# EEZ_DIB_MUX14D_r1B3.net
KiCad netlist of a schematic drawn in EAGLE
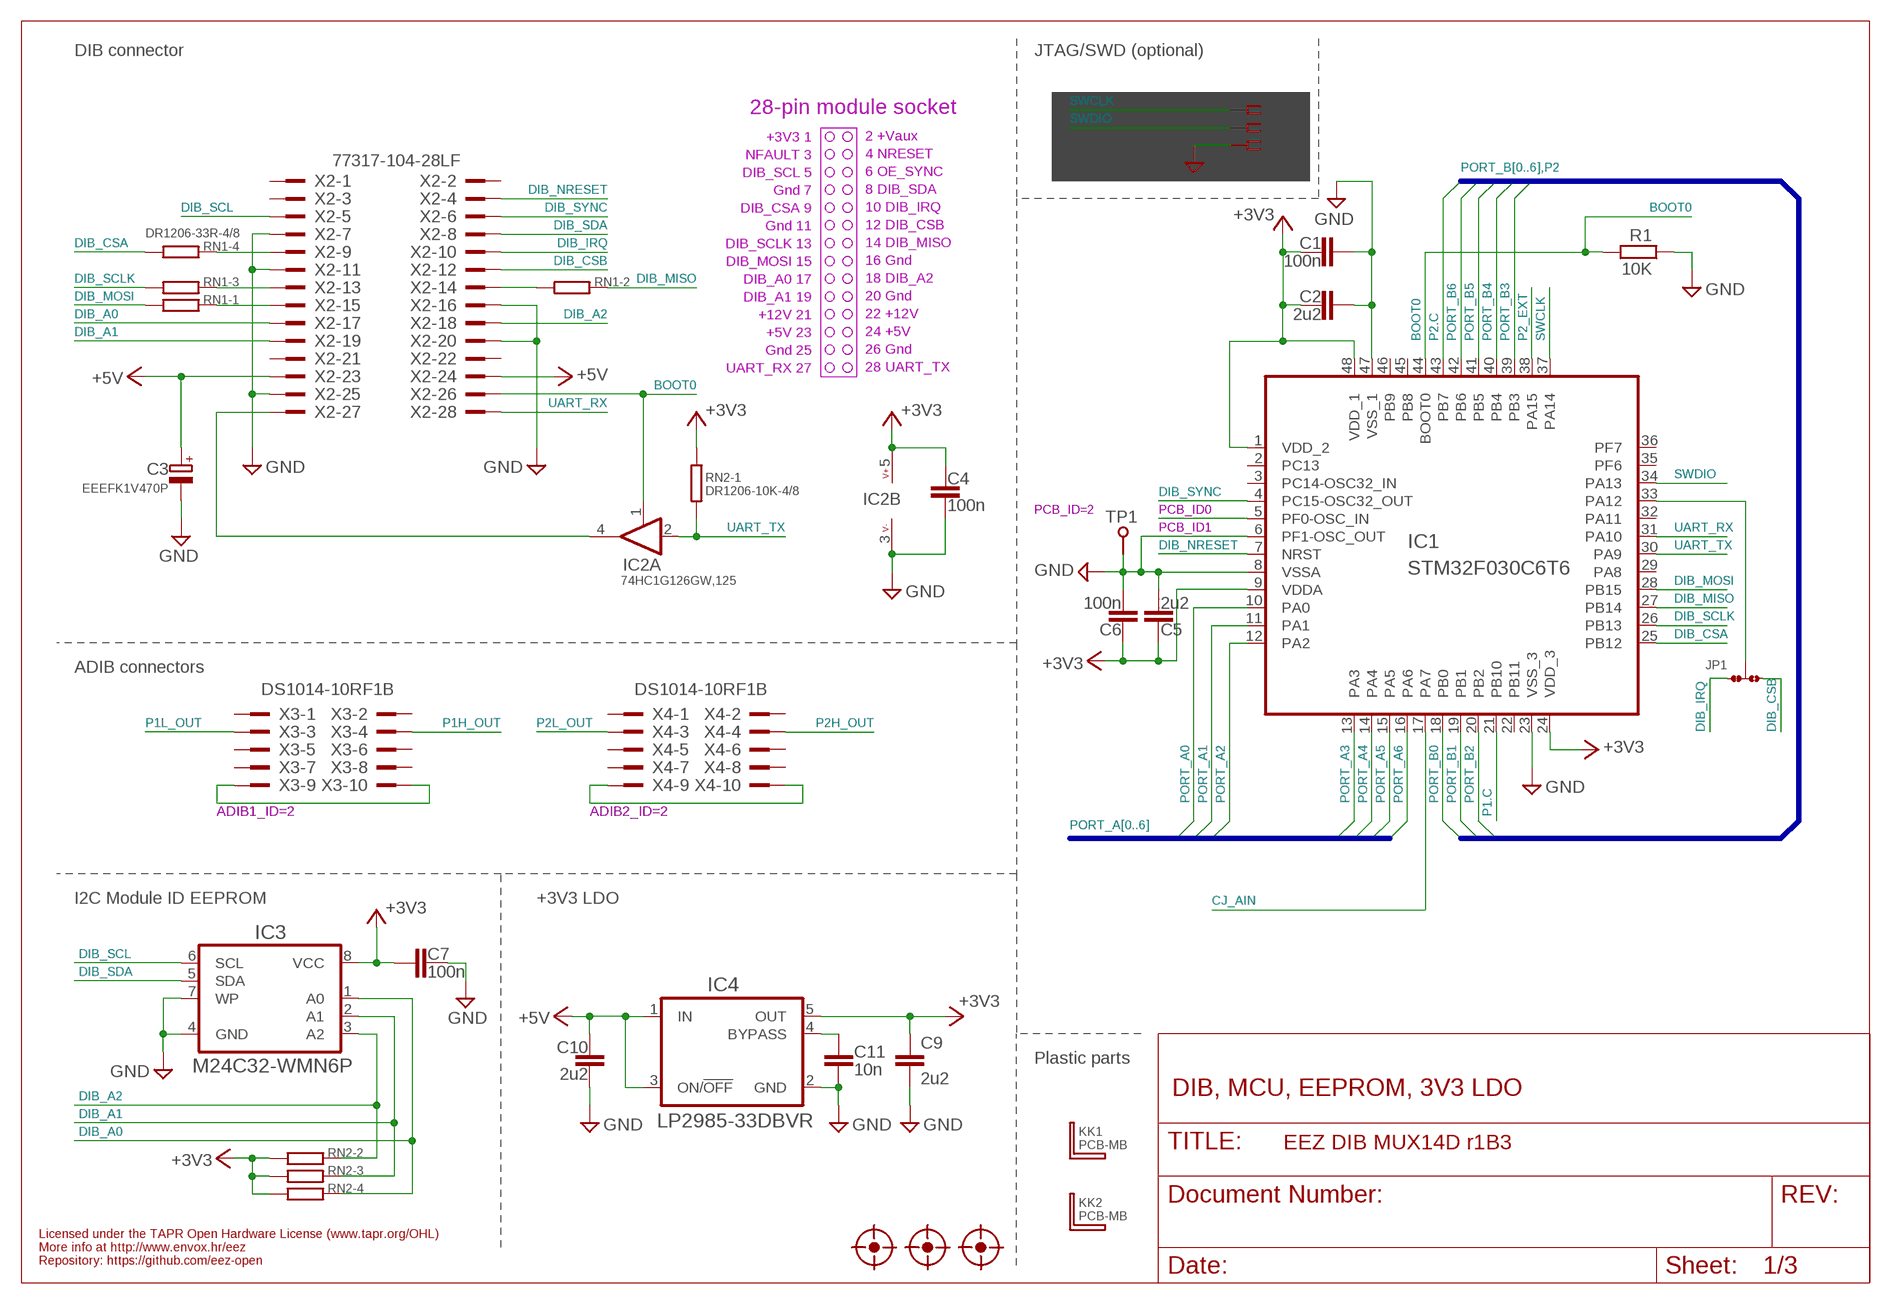
[diagram p0: schematic, sheet 1]
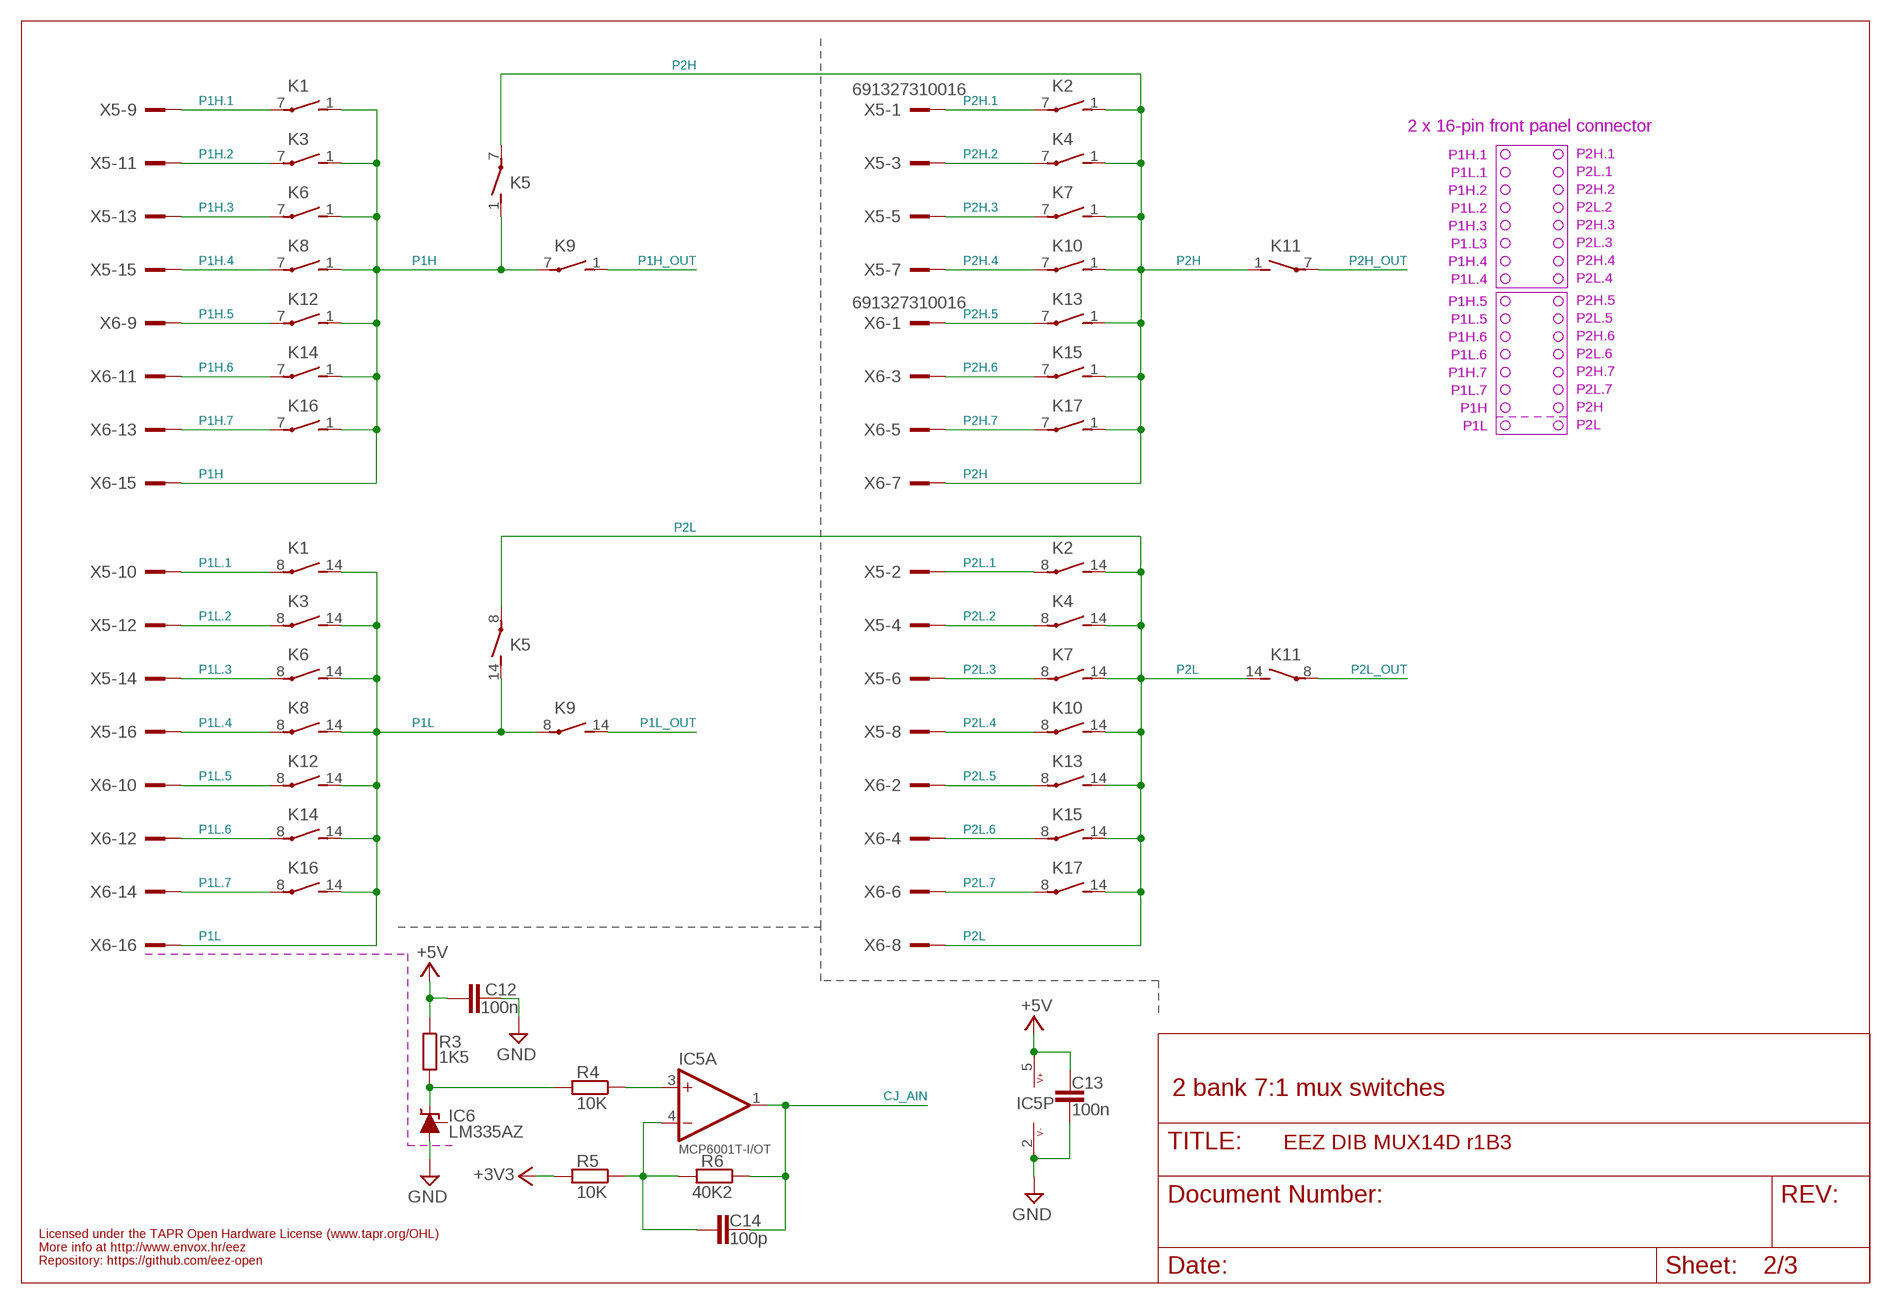
[diagram p1: schematic, sheet 2]
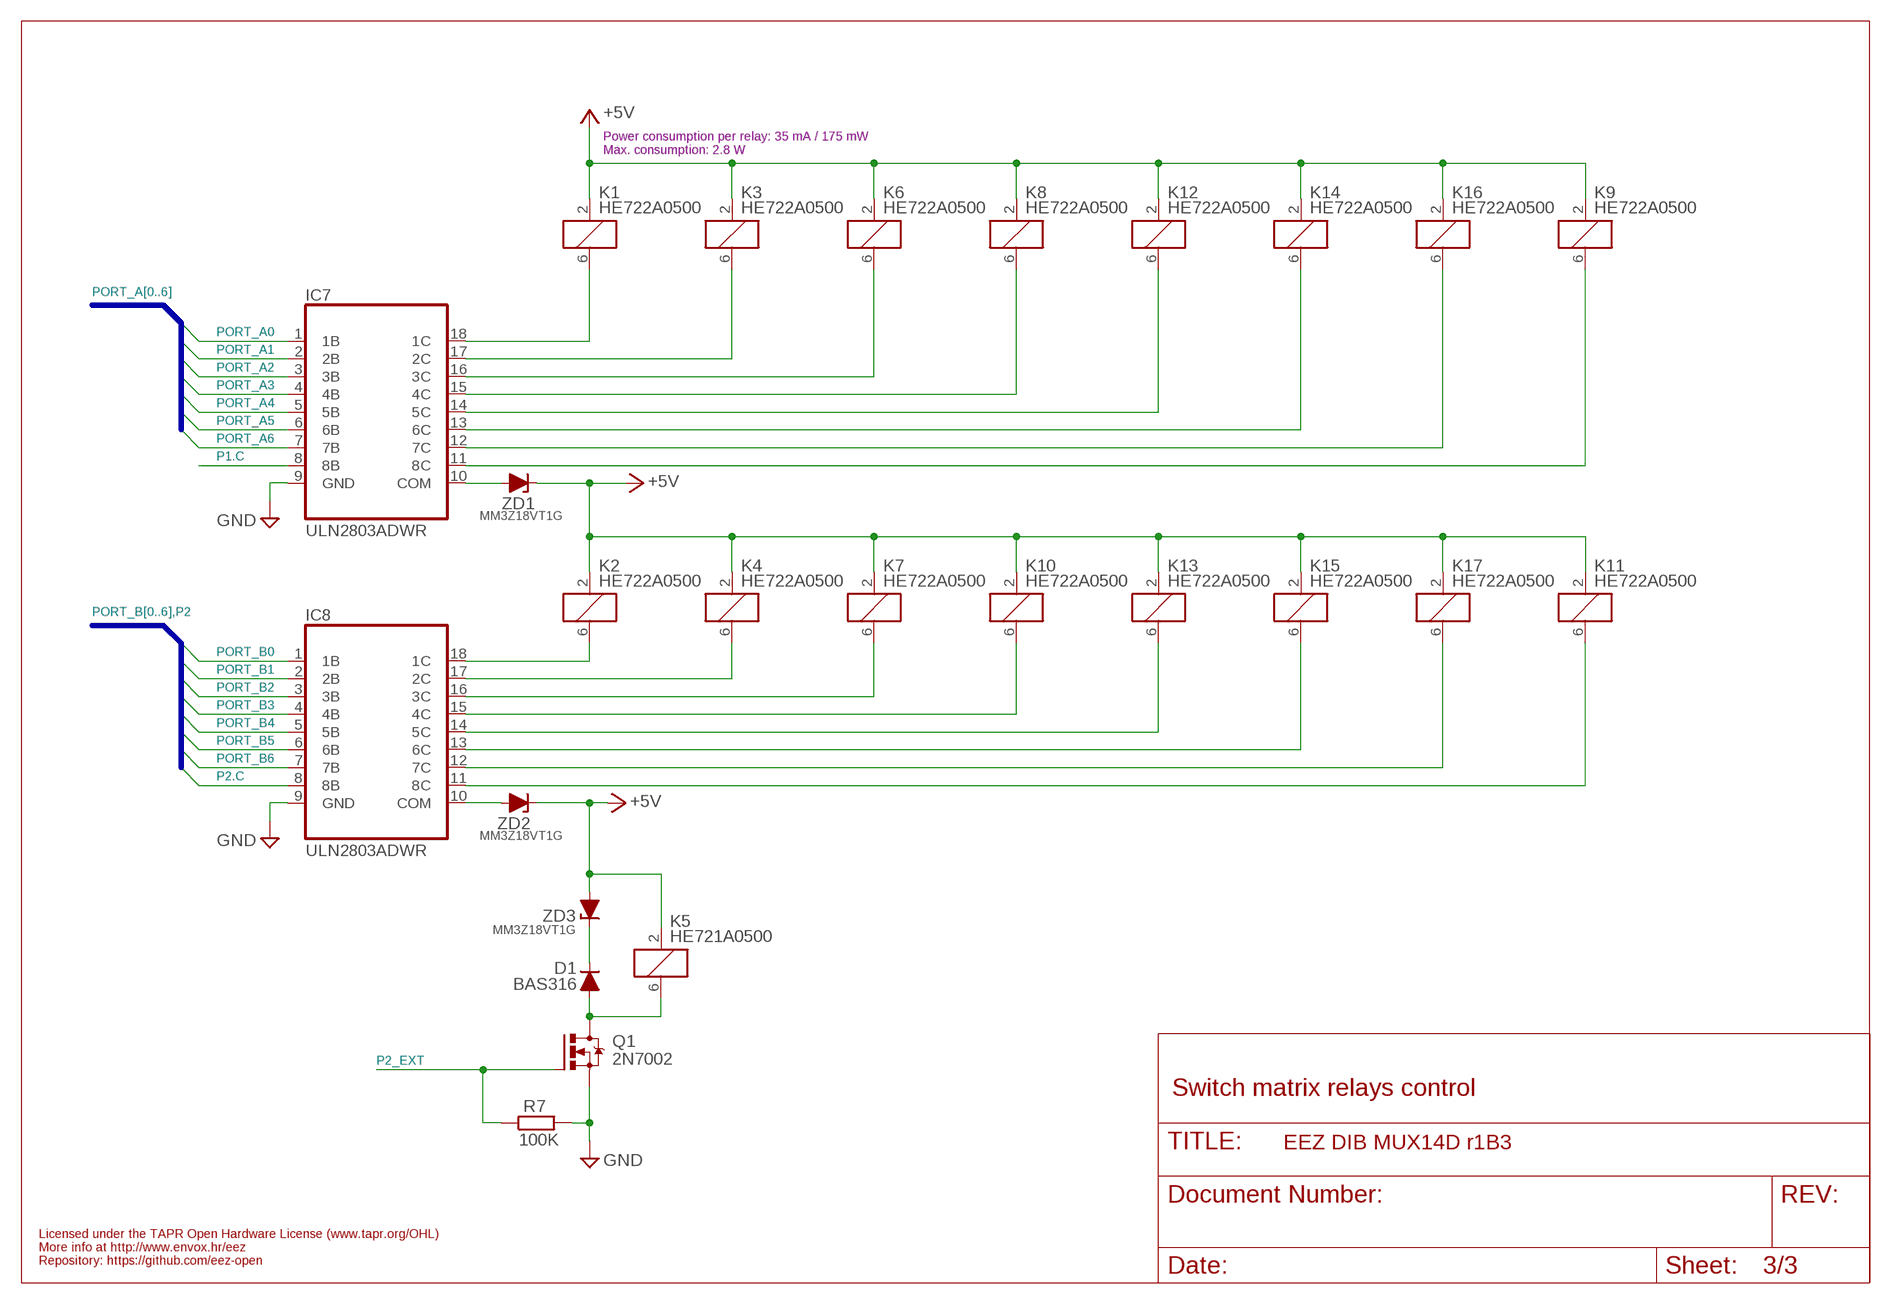
[diagram p2: schematic, sheet 3]

(export (version "E")
  (design (tool "Eeschema 10.0.6"))
  (components
    (comp (ref "C1")
      (value "100n")
      (footprint "eagle-import:C0603")
      (libsource (lib "eagle-import") (part "C-EUC0603"))
    )
    (comp (ref "C2")
      (value "2u2")
      (footprint "eagle-import:C0805")
      (libsource (lib "eagle-import") (part "C-EUC0805"))
    )
    (comp (ref "C3")
      (value "EEEFK1V470P")
      (footprint "eagle-import:CAPAE660X610N")
      (libsource (lib "eagle-import") (part "ECAPPANASONIC_H"))
    )
    (comp (ref "C4")
      (value "100n")
      (footprint "eagle-import:C0603")
      (libsource (lib "eagle-import") (part "C-EUC0603"))
    )
    (comp (ref "C5")
      (value "2u2")
      (footprint "eagle-import:C0805")
      (libsource (lib "eagle-import") (part "C-EUC0805"))
    )
    (comp (ref "C6")
      (value "100n")
      (footprint "eagle-import:C0603")
      (libsource (lib "eagle-import") (part "C-EUC0603"))
    )
    (comp (ref "C7")
      (value "100n")
      (footprint "eagle-import:C0603")
      (libsource (lib "eagle-import") (part "C-EUC0603"))
    )
    (comp (ref "C9")
      (value "2u2")
      (footprint "eagle-import:C0805")
      (libsource (lib "eagle-import") (part "C-EUC0805"))
    )
    (comp (ref "C10")
      (value "2u2")
      (footprint "eagle-import:C0805")
      (libsource (lib "eagle-import") (part "C-EUC0805"))
    )
    (comp (ref "C11")
      (value "10n")
      (footprint "eagle-import:C0805")
      (libsource (lib "eagle-import") (part "C-EUC0805"))
    )
    (comp (ref "FM1")
      (value "FIDUCIAL_2")
      (footprint "eagle-import:FIDUCIAL_DUAL")
      (libsource (lib "eagle-import") (part "FIDUCIAL_2"))
    )
    (comp (ref "FM2")
      (value "FIDUCIAL_2")
      (footprint "eagle-import:FIDUCIAL_DUAL")
      (libsource (lib "eagle-import") (part "FIDUCIAL_2"))
    )
    (comp (ref "FM3")
      (value "FIDUCIAL_2")
      (footprint "eagle-import:FIDUCIAL_DUAL")
      (libsource (lib "eagle-import") (part "FIDUCIAL_2"))
    )
    (comp (ref "IC1")
      (value "STM32F030C6T6")
      (footprint "eagle-import:LQFP-48")
      (libsource (lib "eagle-import") (part "STM32F030C6T6"))
    )
    (comp (ref "IC2")
      (value "74HC1G126GW,125")
      (footprint "eagle-import:SOT65P210X110-5N")
      (libsource (lib "eagle-import") (part "74HC1G126GW,125"))
    )
    (comp (ref "IC3")
      (value "M24C32-WMN6P")
      (footprint "eagle-import:SOIC127P600X173-8N")
      (libsource (lib "eagle-import") (part "AT24CXXSOIC8"))
    )
    (comp (ref "IC4")
      (value "LP2985-33DBVR")
      (footprint "eagle-import:SOT95P270X145-5N")
      (libsource (lib "eagle-import") (part "LP2985"))
    )
    (comp (ref "JP1")
      (value "JP3-CUT-0805-ROTATED")
      (footprint "eagle-import:JP3-0805-CUT2")
      (libsource (lib "eagle-import") (part "JP3-CUT-0805-ROTATED"))
    )
    (comp (ref "KK1")
      (value "PCB-MB")
      (footprint "eagle-import:PCB-MB")
      (libsource (lib "eagle-import") (part "PCB-MB"))
    )
    (comp (ref "KK2")
      (value "PCB-MB")
      (footprint "eagle-import:PCB-MB")
      (libsource (lib "eagle-import") (part "PCB-MB"))
    )
    (comp (ref "R1")
      (value "10K")
      (footprint "eagle-import:R0805")
      (libsource (lib "eagle-import") (part "R-EU_R0805"))
    )
    (comp (ref "RN1")
      (value "DR1206-33R-4/8")
      (footprint "eagle-import:CAY16")
      (libsource (lib "eagle-import") (part "R_ARRAY4"))
    )
    (comp (ref "RN2")
      (value "DR1206-10K-4/8")
      (footprint "eagle-import:CAY16")
      (libsource (lib "eagle-import") (part "R_ARRAY4"))
    )
    (comp (ref "TP1")
      (value "PCB_TEST_TABSHIELD")
      (footprint "eagle-import:PCB_SHIELD_TAB")
      (libsource (lib "eagle-import") (part "PCB_TEST_TABSHIELD"))
    )
    (comp (ref "X1")
      (value "N.C.")
      (footprint "eagle-import:SSW-106-02-S-S")
      (fields (field (name "MPN") "SSW-106-02-S-S"))
      (libsource (lib "eagle-import") (part "SSW-106-02-S-S"))
    )
    (comp (ref "X2")
      (value "77317-104-28LF")
      (footprint "eagle-import:77317-104-28LF")
      (libsource (lib "eagle-import") (part "77317-104-28LF"))
    )
    (comp (ref "X3")
      (value "DS1014-10RF1B")
      (footprint "eagle-import:DS1014-10RF1B")
      (libsource (lib "eagle-import") (part "DS1014-10RF1B"))
    )
    (comp (ref "X4")
      (value "DS1014-10RF1B")
      (footprint "eagle-import:DS1014-10RF1B")
      (libsource (lib "eagle-import") (part "DS1014-10RF1B"))
    )
    (comp (ref "D1")
      (value "BAS316")
      (footprint "eagle-import:SOD323-R")
      (libsource (lib "eagle-import") (part "DIODESOD323R"))
    )
    (comp (ref "IC7")
      (value "ULN2803ADWR")
      (footprint "eagle-import:DW18_TEX-M")
      (libsource (lib "eagle-import") (part "ULN2803ADWR"))
    )
    (comp (ref "IC8")
      (value "ULN2803ADWR")
      (footprint "eagle-import:DW18_TEX-M")
      (libsource (lib "eagle-import") (part "ULN2803ADWR"))
    )
    (comp (ref "K1")
      (value "HE722A0500")
      (footprint "eagle-import:RR2A")
      (libsource (lib "eagle-import") (part "RR2A"))
    )
    (comp (ref "K2")
      (value "HE722A0500")
      (footprint "eagle-import:RR2A")
      (libsource (lib "eagle-import") (part "RR2A"))
    )
    (comp (ref "K3")
      (value "HE722A0500")
      (footprint "eagle-import:RR2A")
      (libsource (lib "eagle-import") (part "RR2A"))
    )
    (comp (ref "K4")
      (value "HE722A0500")
      (footprint "eagle-import:RR2A")
      (libsource (lib "eagle-import") (part "RR2A"))
    )
    (comp (ref "K5")
      (value "HE721A0500")
      (footprint "eagle-import:RR2A")
      (libsource (lib "eagle-import") (part "RR2A"))
    )
    (comp (ref "K6")
      (value "HE722A0500")
      (footprint "eagle-import:RR2A")
      (libsource (lib "eagle-import") (part "RR2A"))
    )
    (comp (ref "K7")
      (value "HE722A0500")
      (footprint "eagle-import:RR2A")
      (libsource (lib "eagle-import") (part "RR2A"))
    )
    (comp (ref "K8")
      (value "HE722A0500")
      (footprint "eagle-import:RR2A")
      (libsource (lib "eagle-import") (part "RR2A"))
    )
    (comp (ref "K9")
      (value "HE722A0500")
      (footprint "eagle-import:RR2A")
      (libsource (lib "eagle-import") (part "RR2A"))
    )
    (comp (ref "K10")
      (value "HE722A0500")
      (footprint "eagle-import:RR2A")
      (libsource (lib "eagle-import") (part "RR2A"))
    )
    (comp (ref "K11")
      (value "HE722A0500")
      (footprint "eagle-import:RR2A")
      (libsource (lib "eagle-import") (part "RR2A"))
    )
    (comp (ref "K12")
      (value "HE722A0500")
      (footprint "eagle-import:RR2A")
      (libsource (lib "eagle-import") (part "RR2A"))
    )
    (comp (ref "K13")
      (value "HE722A0500")
      (footprint "eagle-import:RR2A")
      (libsource (lib "eagle-import") (part "RR2A"))
    )
    (comp (ref "K14")
      (value "HE722A0500")
      (footprint "eagle-import:RR2A")
      (libsource (lib "eagle-import") (part "RR2A"))
    )
    (comp (ref "K15")
      (value "HE722A0500")
      (footprint "eagle-import:RR2A")
      (libsource (lib "eagle-import") (part "RR2A"))
    )
    (comp (ref "K16")
      (value "HE722A0500")
      (footprint "eagle-import:RR2A")
      (libsource (lib "eagle-import") (part "RR2A"))
    )
    (comp (ref "K17")
      (value "HE722A0500")
      (footprint "eagle-import:RR2A")
      (libsource (lib "eagle-import") (part "RR2A"))
    )
    (comp (ref "Q1")
      (value "2N7002")
      (footprint "eagle-import:SOT103P240X110-3N")
      (fields
        (field (name "MPN") "2N7002-7-F")
        (field (name "MPN_1") "2N7002-7-F")
        (field (name "OC_FARNELL") "1713823")
        (field (name "OC_NEWARK") "25R5679")
        (field (name "PACKAGE") "SOT-23-3")
        (field (name "SUPPLIER") "DIODES INC.")
      )
      (libsource (lib "eagle-import") (part "2N7002"))
    )
    (comp (ref "R7")
      (value "100K")
      (footprint "eagle-import:R0805")
      (libsource (lib "eagle-import") (part "R-EU_R0805"))
    )
    (comp (ref "ZD1")
      (value "MM3Z18VT1G")
      (footprint "eagle-import:SOD323-R")
      (libsource (lib "eagle-import") (part "ZENER-DIODESOD323R"))
    )
    (comp (ref "ZD2")
      (value "MM3Z18VT1G")
      (footprint "eagle-import:SOD323-R")
      (libsource (lib "eagle-import") (part "ZENER-DIODESOD323R"))
    )
    (comp (ref "ZD3")
      (value "MM3Z18VT1G")
      (footprint "eagle-import:SOD323-R")
      (libsource (lib "eagle-import") (part "ZENER-DIODESOD323R"))
    )
    (comp (ref "C12")
      (value "100n")
      (footprint "eagle-import:C0603")
      (libsource (lib "eagle-import") (part "C-EUC0603"))
    )
    (comp (ref "C13")
      (value "100n")
      (footprint "eagle-import:C0603")
      (libsource (lib "eagle-import") (part "C-EUC0603"))
    )
    (comp (ref "C14")
      (value "100p")
      (footprint "eagle-import:C0805")
      (libsource (lib "eagle-import") (part "C-EUC0805"))
    )
    (comp (ref "IC5")
      (value "MCP6001T-I/OT")
      (footprint "eagle-import:DBV5")
      (libsource (lib "eagle-import") (part "OPA376AIDBVR"))
    )
    (comp (ref "IC6")
      (value "LM335AZ")
      (footprint "eagle-import:TO92")
      (libsource (lib "eagle-import") (part "LM335-TO92"))
    )
    (comp (ref "R3")
      (value "1K5")
      (footprint "eagle-import:R0805")
      (libsource (lib "eagle-import") (part "R-EU_R0805"))
    )
    (comp (ref "R4")
      (value "10K")
      (footprint "eagle-import:R0805")
      (libsource (lib "eagle-import") (part "R-EU_R0805"))
    )
    (comp (ref "R5")
      (value "10K")
      (footprint "eagle-import:R0805")
      (libsource (lib "eagle-import") (part "R-EU_R0805"))
    )
    (comp (ref "R6")
      (value "40K2")
      (footprint "eagle-import:R0805")
      (libsource (lib "eagle-import") (part "R-EU_R0805"))
    )
    (comp (ref "X5")
      (value "691327310016")
      (footprint "eagle-import:691327310016")
      (libsource (lib "eagle-import") (part "691327310016"))
    )
    (comp (ref "X6")
      (value "691327310016")
      (footprint "eagle-import:691327310016")
      (libsource (lib "eagle-import") (part "691327310016"))
    )
  )
  (nets
    (net (code "3") (name "+3V3") (class "Default")
      (node (ref "C1") (pin "2") (pinfunction "2_2") (pintype "passive"))
      (node (ref "C2") (pin "1") (pinfunction "1_1") (pintype "passive"))
      (node (ref "C4") (pin "1") (pinfunction "1_1") (pintype "passive"))
      (node (ref "C5") (pin "2") (pinfunction "2_2") (pintype "passive"))
      (node (ref "C6") (pin "1") (pinfunction "1_1") (pintype "passive"))
      (node (ref "C7") (pin "2") (pinfunction "2_2") (pintype "passive"))
      (node (ref "C9") (pin "1") (pinfunction "1_1") (pintype "passive"))
      (node (ref "IC1") (pin "1") (pinfunction "VDD_2_1") (pintype "passive"))
      (node (ref "IC1") (pin "24") (pinfunction "VDD_3_24") (pintype "passive"))
      (node (ref "IC1") (pin "48") (pinfunction "VDD_1_48") (pintype "passive"))
      (node (ref "IC1") (pin "9") (pinfunction "VDDA_9") (pintype "passive"))
      (node (ref "IC2") (pin "5") (pinfunction "V+_5") (pintype "power_in"))
      (node (ref "IC3") (pin "8") (pinfunction "VCC_8") (pintype "power_in"))
      (node (ref "IC4") (pin "5") (pinfunction "OUT_5") (pintype "passive"))
      (node (ref "R5") (pin "2") (pinfunction "2_2") (pintype "passive"))
      (node (ref "RN2") (pin "5") (pinfunction "2_5") (pintype "passive"))
      (node (ref "RN2") (pin "6") (pinfunction "2_6") (pintype "passive"))
      (node (ref "RN2") (pin "7") (pinfunction "2_7") (pintype "passive"))
      (node (ref "RN2") (pin "8") (pinfunction "2_8") (pintype "passive"))
    )
    (net (code "4") (name "+5V") (class "Default")
      (node (ref "C10") (pin "2") (pinfunction "2_2") (pintype "passive"))
      (node (ref "C12") (pin "1") (pinfunction "1_1") (pintype "passive"))
      (node (ref "C13") (pin "1") (pinfunction "1_1") (pintype "passive"))
      (node (ref "C3") (pin "1") (pinfunction "+_1") (pintype "passive"))
      (node (ref "IC4") (pin "1") (pinfunction "IN_1") (pintype "input"))
      (node (ref "IC4") (pin "3") (pinfunction "ON/~{OFF}_3") (pintype "input"))
      (node (ref "IC5") (pin "5") (pinfunction "V+_5") (pintype "power_in"))
      (node (ref "K1") (pin "2") (pinfunction "1_2") (pintype "passive"))
      (node (ref "K10") (pin "2") (pinfunction "1_2") (pintype "passive"))
      (node (ref "K11") (pin "2") (pinfunction "1_2") (pintype "passive"))
      (node (ref "K12") (pin "2") (pinfunction "1_2") (pintype "passive"))
      (node (ref "K13") (pin "2") (pinfunction "1_2") (pintype "passive"))
      (node (ref "K14") (pin "2") (pinfunction "1_2") (pintype "passive"))
      (node (ref "K15") (pin "2") (pinfunction "1_2") (pintype "passive"))
      (node (ref "K16") (pin "2") (pinfunction "1_2") (pintype "passive"))
      (node (ref "K17") (pin "2") (pinfunction "1_2") (pintype "passive"))
      (node (ref "K2") (pin "2") (pinfunction "1_2") (pintype "passive"))
      (node (ref "K3") (pin "2") (pinfunction "1_2") (pintype "passive"))
      (node (ref "K4") (pin "2") (pinfunction "1_2") (pintype "passive"))
      (node (ref "K5") (pin "2") (pinfunction "1_2") (pintype "passive"))
      (node (ref "K6") (pin "2") (pinfunction "1_2") (pintype "passive"))
      (node (ref "K7") (pin "2") (pinfunction "1_2") (pintype "passive"))
      (node (ref "K8") (pin "2") (pinfunction "1_2") (pintype "passive"))
      (node (ref "K9") (pin "2") (pinfunction "1_2") (pintype "passive"))
      (node (ref "R3") (pin "1") (pinfunction "1_1") (pintype "passive"))
      (node (ref "X2") (pin "23") (pinfunction "1_23") (pintype "passive"))
      (node (ref "X2") (pin "24") (pinfunction "1_24") (pintype "passive"))
      (node (ref "ZD1") (pin "C") (pinfunction "C_C") (pintype "passive"))
      (node (ref "ZD2") (pin "C") (pinfunction "C_C") (pintype "passive"))
      (node (ref "ZD3") (pin "A") (pinfunction "A_A") (pintype "passive"))
    )
    (net (code "9") (name "BOOT0") (class "Default")
      (node (ref "IC1") (pin "44") (pinfunction "BOOT0_44") (pintype "input"))
      (node (ref "IC2") (pin "1") (pinfunction "EN_1") (pintype "input"))
      (node (ref "R1") (pin "2") (pinfunction "2_2") (pintype "passive"))
      (node (ref "X2") (pin "26") (pinfunction "1_26") (pintype "passive"))
    )
    (net (code "10") (name "CJ_AIN") (class "Default")
      (node (ref "C14") (pin "2") (pinfunction "2_2") (pintype "passive"))
      (node (ref "IC1") (pin "17") (pinfunction "PA7_17") (pintype "bidirectional"))
      (node (ref "IC5") (pin "1") (pinfunction "OUT_1") (pintype "output"))
      (node (ref "R6") (pin "1") (pinfunction "1_1") (pintype "passive"))
    )
    (net (code "11") (name "DIB_A0") (class "Default")
      (node (ref "IC3") (pin "1") (pinfunction "A0_1") (pintype "input"))
      (node (ref "RN2") (pin "4") (pinfunction "1_4") (pintype "passive"))
      (node (ref "X2") (pin "17") (pinfunction "1_17") (pintype "passive"))
    )
    (net (code "12") (name "DIB_A1") (class "Default")
      (node (ref "IC3") (pin "2") (pinfunction "A1_2") (pintype "input"))
      (node (ref "RN2") (pin "3") (pinfunction "1_3") (pintype "passive"))
      (node (ref "X2") (pin "19") (pinfunction "1_19") (pintype "passive"))
    )
    (net (code "13") (name "DIB_A2") (class "Default")
      (node (ref "IC3") (pin "3") (pinfunction "A2_3") (pintype "input"))
      (node (ref "RN2") (pin "2") (pinfunction "1_2") (pintype "passive"))
      (node (ref "X2") (pin "18") (pinfunction "1_18") (pintype "passive"))
    )
    (net (code "14") (name "DIB_CSA") (class "Default")
      (node (ref "IC1") (pin "25") (pinfunction "PB12_25") (pintype "bidirectional"))
      (node (ref "RN1") (pin "4") (pinfunction "1_4") (pintype "passive"))
    )
    (net (code "15") (name "DIB_CSB") (class "Default")
      (node (ref "JP1") (pin "NO") (pinfunction "NO_NO") (pintype "passive"))
      (node (ref "X2") (pin "12") (pinfunction "1_12") (pintype "passive"))
    )
    (net (code "16") (name "DIB_IRQ") (class "Default")
      (node (ref "JP1") (pin "NC") (pinfunction "NC_NC") (pintype "passive"))
      (node (ref "X2") (pin "10") (pinfunction "1_10") (pintype "passive"))
    )
    (net (code "17") (name "DIB_MISO") (class "Default")
      (node (ref "IC1") (pin "27") (pinfunction "PB14_27") (pintype "bidirectional"))
      (node (ref "RN1") (pin "2") (pinfunction "1_2") (pintype "passive"))
    )
    (net (code "18") (name "DIB_MOSI") (class "Default")
      (node (ref "IC1") (pin "28") (pinfunction "PB15_28") (pintype "bidirectional"))
      (node (ref "RN1") (pin "1") (pinfunction "1_1") (pintype "passive"))
    )
    (net (code "19") (name "DIB_NRESET") (class "Default")
      (node (ref "IC1") (pin "7") (pinfunction "NRST_7") (pintype "input"))
      (node (ref "X2") (pin "4") (pinfunction "1_4") (pintype "passive"))
    )
    (net (code "20") (name "DIB_SCL") (class "Default")
      (node (ref "IC3") (pin "6") (pinfunction "SCL_6") (pintype "bidirectional"))
      (node (ref "X2") (pin "5") (pinfunction "1_5") (pintype "passive"))
    )
    (net (code "21") (name "DIB_SCLK") (class "Default")
      (node (ref "IC1") (pin "26") (pinfunction "PB13_26") (pintype "bidirectional"))
      (node (ref "RN1") (pin "3") (pinfunction "1_3") (pintype "passive"))
    )
    (net (code "22") (name "DIB_SDA") (class "Default")
      (node (ref "IC3") (pin "5") (pinfunction "SDA_5") (pintype "bidirectional"))
      (node (ref "X2") (pin "8") (pinfunction "1_8") (pintype "passive"))
    )
    (net (code "23") (name "DIB_SYNC") (class "Default")
      (node (ref "IC1") (pin "4") (pinfunction "PC15-OSC32_OUT_4") (pintype "bidirectional"))
      (node (ref "X2") (pin "6") (pinfunction "1_6") (pintype "passive"))
    )
    (net (code "24") (name "GND") (class "Default")
      (node (ref "C1") (pin "1") (pinfunction "1_1") (pintype "passive"))
      (node (ref "C10") (pin "1") (pinfunction "1_1") (pintype "passive"))
      (node (ref "C11") (pin "1") (pinfunction "1_1") (pintype "passive"))
      (node (ref "C12") (pin "2") (pinfunction "2_2") (pintype "passive"))
      (node (ref "C13") (pin "2") (pinfunction "2_2") (pintype "passive"))
      (node (ref "C2") (pin "2") (pinfunction "2_2") (pintype "passive"))
      (node (ref "C3") (pin "2") (pinfunction "-_2") (pintype "passive"))
      (node (ref "C4") (pin "2") (pinfunction "2_2") (pintype "passive"))
      (node (ref "C5") (pin "1") (pinfunction "1_1") (pintype "passive"))
      (node (ref "C6") (pin "2") (pinfunction "2_2") (pintype "passive"))
      (node (ref "C7") (pin "1") (pinfunction "1_1") (pintype "passive"))
      (node (ref "C9") (pin "2") (pinfunction "2_2") (pintype "passive"))
      (node (ref "IC1") (pin "23") (pinfunction "VSS_3_23") (pintype "passive"))
      (node (ref "IC1") (pin "47") (pinfunction "VSS_1_47") (pintype "passive"))
      (node (ref "IC1") (pin "6") (pinfunction "PF1-OSC_OUT_6") (pintype "bidirectional"))
      (node (ref "IC1") (pin "8") (pinfunction "VSSA_8") (pintype "passive"))
      (node (ref "IC2") (pin "3") (pinfunction "V-_3") (pintype "power_in"))
      (node (ref "IC3") (pin "4") (pinfunction "GND_4") (pintype "passive"))
      (node (ref "IC3") (pin "7") (pinfunction "WP_7") (pintype "input"))
      (node (ref "IC4") (pin "2") (pinfunction "GND_2") (pintype "passive"))
      (node (ref "IC5") (pin "2") (pinfunction "V-_2") (pintype "power_in"))
      (node (ref "IC6") (pin "3") (pinfunction "A_3") (pintype "passive"))
      (node (ref "IC7") (pin "9") (pinfunction "GND_9") (pintype "input"))
      (node (ref "IC8") (pin "9") (pinfunction "GND_9") (pintype "input"))
      (node (ref "Q1") (pin "2") (pinfunction "S_2") (pintype "passive"))
      (node (ref "R1") (pin "1") (pinfunction "1_1") (pintype "passive"))
      (node (ref "R7") (pin "2") (pinfunction "2_2") (pintype "passive"))
      (node (ref "TP1") (pin "1") (pinfunction "P$1_1") (pintype "bidirectional"))
      (node (ref "X1") (pin "3") (pinfunction "1_3") (pintype "passive"))
      (node (ref "X2") (pin "11") (pinfunction "1_11") (pintype "passive"))
      (node (ref "X2") (pin "16") (pinfunction "1_16") (pintype "passive"))
      (node (ref "X2") (pin "20") (pinfunction "1_20") (pintype "passive"))
      (node (ref "X2") (pin "25") (pinfunction "1_25") (pintype "passive"))
      (node (ref "X2") (pin "7") (pinfunction "1_7") (pintype "passive"))
    )
    (net (code "25") (name "Net-(D1-PadC)") (class "Default")
      (node (ref "D1") (pin "C") (pinfunction "C_C") (pintype "passive"))
      (node (ref "ZD3") (pin "C") (pinfunction "C_C") (pintype "passive"))
    )
    (net (code "26") (name "Net-(IC1-PA12)") (class "Default")
      (node (ref "IC1") (pin "33") (pinfunction "PA12_33") (pintype "bidirectional"))
      (node (ref "JP1") (pin "COM") (pinfunction "COM_COM") (pintype "passive"))
    )
    (net (code "27") (name "Net-(IC2A-O)") (class "Default")
      (node (ref "IC2") (pin "4") (pinfunction "O_4") (pintype "output"))
      (node (ref "X2") (pin "27") (pinfunction "1_27") (pintype "passive"))
    )
    (net (code "28") (name "Net-(IC4-BYPASS)") (class "Default")
      (node (ref "C11") (pin "2") (pinfunction "2_2") (pintype "passive"))
      (node (ref "IC4") (pin "4") (pinfunction "BYPASS_4") (pintype "passive"))
    )
    (net (code "29") (name "Net-(IC5A-+IN)") (class "Default")
      (node (ref "IC5") (pin "3") (pinfunction "+IN_3") (pintype "input"))
      (node (ref "R4") (pin "1") (pinfunction "1_1") (pintype "passive"))
    )
    (net (code "30") (name "Net-(IC5A--IN)") (class "Default")
      (node (ref "C14") (pin "1") (pinfunction "1_1") (pintype "passive"))
      (node (ref "IC5") (pin "4") (pinfunction "-IN_4") (pintype "input"))
      (node (ref "R5") (pin "1") (pinfunction "1_1") (pintype "passive"))
      (node (ref "R6") (pin "2") (pinfunction "2_2") (pintype "passive"))
    )
    (net (code "31") (name "Net-(IC6-C)") (class "Default")
      (node (ref "IC6") (pin "2") (pinfunction "C_2") (pintype "passive"))
      (node (ref "R3") (pin "2") (pinfunction "2_2") (pintype "passive"))
      (node (ref "R4") (pin "2") (pinfunction "2_2") (pintype "passive"))
    )
    (net (code "32") (name "Net-(IC7-1C)") (class "Default")
      (node (ref "IC7") (pin "18") (pinfunction "1C_18") (pintype "output"))
      (node (ref "K1") (pin "6") (pinfunction "2_6") (pintype "passive"))
    )
    (net (code "33") (name "Net-(IC7-2C)") (class "Default")
      (node (ref "IC7") (pin "17") (pinfunction "2C_17") (pintype "output"))
      (node (ref "K3") (pin "6") (pinfunction "2_6") (pintype "passive"))
    )
    (net (code "34") (name "Net-(IC7-3C)") (class "Default")
      (node (ref "IC7") (pin "16") (pinfunction "3C_16") (pintype "output"))
      (node (ref "K6") (pin "6") (pinfunction "2_6") (pintype "passive"))
    )
    (net (code "35") (name "Net-(IC7-4C)") (class "Default")
      (node (ref "IC7") (pin "15") (pinfunction "4C_15") (pintype "output"))
      (node (ref "K8") (pin "6") (pinfunction "2_6") (pintype "passive"))
    )
    (net (code "36") (name "Net-(IC7-5C)") (class "Default")
      (node (ref "IC7") (pin "14") (pinfunction "5C_14") (pintype "output"))
      (node (ref "K12") (pin "6") (pinfunction "2_6") (pintype "passive"))
    )
    (net (code "37") (name "Net-(IC7-6C)") (class "Default")
      (node (ref "IC7") (pin "13") (pinfunction "6C_13") (pintype "output"))
      (node (ref "K14") (pin "6") (pinfunction "2_6") (pintype "passive"))
    )
    (net (code "38") (name "Net-(IC7-7C)") (class "Default")
      (node (ref "IC7") (pin "12") (pinfunction "7C_12") (pintype "output"))
      (node (ref "K16") (pin "6") (pinfunction "2_6") (pintype "passive"))
    )
    (net (code "39") (name "Net-(IC7-8C)") (class "Default")
      (node (ref "IC7") (pin "11") (pinfunction "8C_11") (pintype "output"))
      (node (ref "K9") (pin "6") (pinfunction "2_6") (pintype "passive"))
    )
    (net (code "40") (name "Net-(IC7-COM)") (class "Default")
      (node (ref "IC7") (pin "10") (pinfunction "COM_10") (pintype "passive"))
      (node (ref "ZD1") (pin "A") (pinfunction "A_A") (pintype "passive"))
    )
    (net (code "41") (name "Net-(IC8-1C)") (class "Default")
      (node (ref "IC8") (pin "18") (pinfunction "1C_18") (pintype "output"))
      (node (ref "K2") (pin "6") (pinfunction "2_6") (pintype "passive"))
    )
    (net (code "42") (name "Net-(IC8-2C)") (class "Default")
      (node (ref "IC8") (pin "17") (pinfunction "2C_17") (pintype "output"))
      (node (ref "K4") (pin "6") (pinfunction "2_6") (pintype "passive"))
    )
    (net (code "43") (name "Net-(IC8-3C)") (class "Default")
      (node (ref "IC8") (pin "16") (pinfunction "3C_16") (pintype "output"))
      (node (ref "K7") (pin "6") (pinfunction "2_6") (pintype "passive"))
    )
    (net (code "44") (name "Net-(IC8-4C)") (class "Default")
      (node (ref "IC8") (pin "15") (pinfunction "4C_15") (pintype "output"))
      (node (ref "K10") (pin "6") (pinfunction "2_6") (pintype "passive"))
    )
    (net (code "45") (name "Net-(IC8-5C)") (class "Default")
      (node (ref "IC8") (pin "14") (pinfunction "5C_14") (pintype "output"))
      (node (ref "K13") (pin "6") (pinfunction "2_6") (pintype "passive"))
    )
    (net (code "46") (name "Net-(IC8-6C)") (class "Default")
      (node (ref "IC8") (pin "13") (pinfunction "6C_13") (pintype "output"))
      (node (ref "K15") (pin "6") (pinfunction "2_6") (pintype "passive"))
    )
    (net (code "47") (name "Net-(IC8-7C)") (class "Default")
      (node (ref "IC8") (pin "12") (pinfunction "7C_12") (pintype "output"))
      (node (ref "K17") (pin "6") (pinfunction "2_6") (pintype "passive"))
    )
    (net (code "48") (name "Net-(IC8-8C)") (class "Default")
      (node (ref "IC8") (pin "11") (pinfunction "8C_11") (pintype "output"))
      (node (ref "K11") (pin "6") (pinfunction "2_6") (pintype "passive"))
    )
    (net (code "49") (name "Net-(IC8-COM)") (class "Default")
      (node (ref "IC8") (pin "10") (pinfunction "COM_10") (pintype "passive"))
      (node (ref "ZD2") (pin "A") (pinfunction "A_A") (pintype "passive"))
    )
    (net (code "50") (name "Net-(K5A-2)") (class "Default")
      (node (ref "D1") (pin "A") (pinfunction "A_A") (pintype "passive"))
      (node (ref "K5") (pin "6") (pinfunction "2_6") (pintype "passive"))
      (node (ref "Q1") (pin "3") (pinfunction "D_3") (pintype "passive"))
    )
    (net (code "51") (name "Net-(RN1A-2)") (class "Default")
      (node (ref "RN1") (pin "8") (pinfunction "2_8") (pintype "passive"))
      (node (ref "X2") (pin "15") (pinfunction "1_15") (pintype "passive"))
    )
    (net (code "52") (name "Net-(RN1B-2)") (class "Default")
      (node (ref "RN1") (pin "7") (pinfunction "2_7") (pintype "passive"))
      (node (ref "X2") (pin "14") (pinfunction "1_14") (pintype "passive"))
    )
    (net (code "53") (name "Net-(RN1C-2)") (class "Default")
      (node (ref "RN1") (pin "6") (pinfunction "2_6") (pintype "passive"))
      (node (ref "X2") (pin "13") (pinfunction "1_13") (pintype "passive"))
    )
    (net (code "54") (name "Net-(RN1D-2)") (class "Default")
      (node (ref "RN1") (pin "5") (pinfunction "2_5") (pintype "passive"))
      (node (ref "X2") (pin "9") (pinfunction "1_9") (pintype "passive"))
    )
    (net (code "55") (name "Net-(X3B-1)") (class "Default")
      (node (ref "X3") (pin "10") (pinfunction "1_10") (pintype "passive"))
      (node (ref "X3") (pin "9") (pinfunction "1_9") (pintype "passive"))
    )
    (net (code "56") (name "Net-(X4B-1)") (class "Default")
      (node (ref "X4") (pin "10") (pinfunction "1_10") (pintype "passive"))
      (node (ref "X4") (pin "9") (pinfunction "1_9") (pintype "passive"))
    )
    (net (code "57") (name "P1.C") (class "Default")
      (node (ref "IC1") (pin "21") (pinfunction "PB10_21") (pintype "bidirectional"))
      (node (ref "IC7") (pin "8") (pinfunction "8B_8") (pintype "input"))
    )
    (net (code "58") (name "P1H") (class "Default")
      (node (ref "K1") (pin "1") (pinfunction "S_1") (pintype "passive"))
      (node (ref "K12") (pin "1") (pinfunction "S_1") (pintype "passive"))
      (node (ref "K14") (pin "1") (pinfunction "S_1") (pintype "passive"))
      (node (ref "K16") (pin "1") (pinfunction "S_1") (pintype "passive"))
      (node (ref "K3") (pin "1") (pinfunction "S_1") (pintype "passive"))
      (node (ref "K5") (pin "1") (pinfunction "S_1") (pintype "passive"))
      (node (ref "K6") (pin "1") (pinfunction "S_1") (pintype "passive"))
      (node (ref "K8") (pin "1") (pinfunction "S_1") (pintype "passive"))
      (node (ref "K9") (pin "7") (pinfunction "P_7") (pintype "passive"))
      (node (ref "X6") (pin "15") (pinfunction "1_15") (pintype "passive"))
    )
    (net (code "59") (name "P1H.1") (class "Default")
      (node (ref "K1") (pin "7") (pinfunction "P_7") (pintype "passive"))
      (node (ref "X5") (pin "9") (pinfunction "1_9") (pintype "passive"))
    )
    (net (code "60") (name "P1H.2") (class "Default")
      (node (ref "K3") (pin "7") (pinfunction "P_7") (pintype "passive"))
      (node (ref "X5") (pin "11") (pinfunction "1_11") (pintype "passive"))
    )
    (net (code "61") (name "P1H.3") (class "Default")
      (node (ref "K6") (pin "7") (pinfunction "P_7") (pintype "passive"))
      (node (ref "X5") (pin "13") (pinfunction "1_13") (pintype "passive"))
    )
    (net (code "62") (name "P1H.4") (class "Default")
      (node (ref "K8") (pin "7") (pinfunction "P_7") (pintype "passive"))
      (node (ref "X5") (pin "15") (pinfunction "1_15") (pintype "passive"))
    )
    (net (code "63") (name "P1H.5") (class "Default")
      (node (ref "K12") (pin "7") (pinfunction "P_7") (pintype "passive"))
      (node (ref "X6") (pin "9") (pinfunction "1_9") (pintype "passive"))
    )
    (net (code "64") (name "P1H.6") (class "Default")
      (node (ref "K14") (pin "7") (pinfunction "P_7") (pintype "passive"))
      (node (ref "X6") (pin "11") (pinfunction "1_11") (pintype "passive"))
    )
    (net (code "65") (name "P1H.7") (class "Default")
      (node (ref "K16") (pin "7") (pinfunction "P_7") (pintype "passive"))
      (node (ref "X6") (pin "13") (pinfunction "1_13") (pintype "passive"))
    )
    (net (code "66") (name "P1H_OUT") (class "Default")
      (node (ref "K9") (pin "1") (pinfunction "S_1") (pintype "passive"))
      (node (ref "X3") (pin "4") (pinfunction "1_4") (pintype "passive"))
    )
    (net (code "67") (name "P1L") (class "Default")
      (node (ref "K1") (pin "14") (pinfunction "S_14") (pintype "passive"))
      (node (ref "K12") (pin "14") (pinfunction "S_14") (pintype "passive"))
      (node (ref "K14") (pin "14") (pinfunction "S_14") (pintype "passive"))
      (node (ref "K16") (pin "14") (pinfunction "S_14") (pintype "passive"))
      (node (ref "K3") (pin "14") (pinfunction "S_14") (pintype "passive"))
      (node (ref "K5") (pin "14") (pinfunction "S_14") (pintype "passive"))
      (node (ref "K6") (pin "14") (pinfunction "S_14") (pintype "passive"))
      (node (ref "K8") (pin "14") (pinfunction "S_14") (pintype "passive"))
      (node (ref "K9") (pin "8") (pinfunction "P_8") (pintype "passive"))
      (node (ref "X6") (pin "16") (pinfunction "1_16") (pintype "passive"))
    )
    (net (code "68") (name "P1L.1") (class "Default")
      (node (ref "K1") (pin "8") (pinfunction "P_8") (pintype "passive"))
      (node (ref "X5") (pin "10") (pinfunction "1_10") (pintype "passive"))
    )
    (net (code "69") (name "P1L.2") (class "Default")
      (node (ref "K3") (pin "8") (pinfunction "P_8") (pintype "passive"))
      (node (ref "X5") (pin "12") (pinfunction "1_12") (pintype "passive"))
    )
    (net (code "70") (name "P1L.3") (class "Default")
      (node (ref "K6") (pin "8") (pinfunction "P_8") (pintype "passive"))
      (node (ref "X5") (pin "14") (pinfunction "1_14") (pintype "passive"))
    )
    (net (code "71") (name "P1L.4") (class "Default")
      (node (ref "K8") (pin "8") (pinfunction "P_8") (pintype "passive"))
      (node (ref "X5") (pin "16") (pinfunction "1_16") (pintype "passive"))
    )
    (net (code "72") (name "P1L.5") (class "Default")
      (node (ref "K12") (pin "8") (pinfunction "P_8") (pintype "passive"))
      (node (ref "X6") (pin "10") (pinfunction "1_10") (pintype "passive"))
    )
    (net (code "73") (name "P1L.6") (class "Default")
      (node (ref "K14") (pin "8") (pinfunction "P_8") (pintype "passive"))
      (node (ref "X6") (pin "12") (pinfunction "1_12") (pintype "passive"))
    )
    (net (code "74") (name "P1L.7") (class "Default")
      (node (ref "K16") (pin "8") (pinfunction "P_8") (pintype "passive"))
      (node (ref "X6") (pin "14") (pinfunction "1_14") (pintype "passive"))
    )
    (net (code "75") (name "P1L_OUT") (class "Default")
      (node (ref "K9") (pin "14") (pinfunction "S_14") (pintype "passive"))
      (node (ref "X3") (pin "3") (pinfunction "1_3") (pintype "passive"))
    )
    (net (code "76") (name "P2.C") (class "Default")
      (node (ref "IC1") (pin "43") (pinfunction "PB7_43") (pintype "bidirectional"))
      (node (ref "IC8") (pin "8") (pinfunction "8B_8") (pintype "input"))
    )
    (net (code "77") (name "P2H") (class "Default")
      (node (ref "K10") (pin "1") (pinfunction "S_1") (pintype "passive"))
      (node (ref "K11") (pin "1") (pinfunction "S_1") (pintype "passive"))
      (node (ref "K13") (pin "1") (pinfunction "S_1") (pintype "passive"))
      (node (ref "K15") (pin "1") (pinfunction "S_1") (pintype "passive"))
      (node (ref "K17") (pin "1") (pinfunction "S_1") (pintype "passive"))
      (node (ref "K2") (pin "1") (pinfunction "S_1") (pintype "passive"))
      (node (ref "K4") (pin "1") (pinfunction "S_1") (pintype "passive"))
      (node (ref "K5") (pin "7") (pinfunction "P_7") (pintype "passive"))
      (node (ref "K7") (pin "1") (pinfunction "S_1") (pintype "passive"))
      (node (ref "X6") (pin "7") (pinfunction "1_7") (pintype "passive"))
    )
    (net (code "78") (name "P2H.1") (class "Default")
      (node (ref "K2") (pin "7") (pinfunction "P_7") (pintype "passive"))
      (node (ref "X5") (pin "1") (pinfunction "1_1") (pintype "passive"))
    )
    (net (code "79") (name "P2H.2") (class "Default")
      (node (ref "K4") (pin "7") (pinfunction "P_7") (pintype "passive"))
      (node (ref "X5") (pin "3") (pinfunction "1_3") (pintype "passive"))
    )
    (net (code "80") (name "P2H.3") (class "Default")
      (node (ref "K7") (pin "7") (pinfunction "P_7") (pintype "passive"))
      (node (ref "X5") (pin "5") (pinfunction "1_5") (pintype "passive"))
    )
    (net (code "81") (name "P2H.4") (class "Default")
      (node (ref "K10") (pin "7") (pinfunction "P_7") (pintype "passive"))
      (node (ref "X5") (pin "7") (pinfunction "1_7") (pintype "passive"))
    )
    (net (code "82") (name "P2H.5") (class "Default")
      (node (ref "K13") (pin "7") (pinfunction "P_7") (pintype "passive"))
      (node (ref "X6") (pin "1") (pinfunction "1_1") (pintype "passive"))
    )
    (net (code "83") (name "P2H.6") (class "Default")
      (node (ref "K15") (pin "7") (pinfunction "P_7") (pintype "passive"))
      (node (ref "X6") (pin "3") (pinfunction "1_3") (pintype "passive"))
    )
    (net (code "84") (name "P2H.7") (class "Default")
      (node (ref "K17") (pin "7") (pinfunction "P_7") (pintype "passive"))
      (node (ref "X6") (pin "5") (pinfunction "1_5") (pintype "passive"))
    )
    (net (code "85") (name "P2H_OUT") (class "Default")
      (node (ref "K11") (pin "7") (pinfunction "P_7") (pintype "passive"))
      (node (ref "X4") (pin "4") (pinfunction "1_4") (pintype "passive"))
    )
    (net (code "86") (name "P2L") (class "Default")
      (node (ref "K10") (pin "14") (pinfunction "S_14") (pintype "passive"))
      (node (ref "K11") (pin "14") (pinfunction "S_14") (pintype "passive"))
      (node (ref "K13") (pin "14") (pinfunction "S_14") (pintype "passive"))
      (node (ref "K15") (pin "14") (pinfunction "S_14") (pintype "passive"))
      (node (ref "K17") (pin "14") (pinfunction "S_14") (pintype "passive"))
      (node (ref "K2") (pin "14") (pinfunction "S_14") (pintype "passive"))
      (node (ref "K4") (pin "14") (pinfunction "S_14") (pintype "passive"))
      (node (ref "K5") (pin "8") (pinfunction "P_8") (pintype "passive"))
      (node (ref "K7") (pin "14") (pinfunction "S_14") (pintype "passive"))
      (node (ref "X6") (pin "8") (pinfunction "1_8") (pintype "passive"))
    )
    (net (code "87") (name "P2L.1") (class "Default")
      (node (ref "K2") (pin "8") (pinfunction "P_8") (pintype "passive"))
      (node (ref "X5") (pin "2") (pinfunction "1_2") (pintype "passive"))
    )
    (net (code "88") (name "P2L.2") (class "Default")
      (node (ref "K4") (pin "8") (pinfunction "P_8") (pintype "passive"))
      (node (ref "X5") (pin "4") (pinfunction "1_4") (pintype "passive"))
    )
    (net (code "89") (name "P2L.3") (class "Default")
      (node (ref "K7") (pin "8") (pinfunction "P_8") (pintype "passive"))
      (node (ref "X5") (pin "6") (pinfunction "1_6") (pintype "passive"))
    )
    (net (code "90") (name "P2L.4") (class "Default")
      (node (ref "K10") (pin "8") (pinfunction "P_8") (pintype "passive"))
      (node (ref "X5") (pin "8") (pinfunction "1_8") (pintype "passive"))
    )
    (net (code "91") (name "P2L.5") (class "Default")
      (node (ref "K13") (pin "8") (pinfunction "P_8") (pintype "passive"))
      (node (ref "X6") (pin "2") (pinfunction "1_2") (pintype "passive"))
    )
    (net (code "92") (name "P2L.6") (class "Default")
      (node (ref "K15") (pin "8") (pinfunction "P_8") (pintype "passive"))
      (node (ref "X6") (pin "4") (pinfunction "1_4") (pintype "passive"))
    )
    (net (code "93") (name "P2L.7") (class "Default")
      (node (ref "K17") (pin "8") (pinfunction "P_8") (pintype "passive"))
      (node (ref "X6") (pin "6") (pinfunction "1_6") (pintype "passive"))
    )
    (net (code "94") (name "P2L_OUT") (class "Default")
      (node (ref "K11") (pin "8") (pinfunction "P_8") (pintype "passive"))
      (node (ref "X4") (pin "3") (pinfunction "1_3") (pintype "passive"))
    )
    (net (code "95") (name "P2_EXT") (class "Default")
      (node (ref "IC1") (pin "38") (pinfunction "PA15_38") (pintype "bidirectional"))
      (node (ref "Q1") (pin "1") (pinfunction "G_1") (pintype "passive"))
      (node (ref "R7") (pin "1") (pinfunction "1_1") (pintype "passive"))
    )
    (net (code "96") (name "PORT_A0") (class "Default")
      (node (ref "IC1") (pin "10") (pinfunction "PA0_10") (pintype "bidirectional"))
      (node (ref "IC7") (pin "1") (pinfunction "1B_1") (pintype "input"))
    )
    (net (code "97") (name "PORT_A1") (class "Default")
      (node (ref "IC1") (pin "11") (pinfunction "PA1_11") (pintype "bidirectional"))
      (node (ref "IC7") (pin "2") (pinfunction "2B_2") (pintype "input"))
    )
    (net (code "98") (name "PORT_A2") (class "Default")
      (node (ref "IC1") (pin "12") (pinfunction "PA2_12") (pintype "bidirectional"))
      (node (ref "IC7") (pin "3") (pinfunction "3B_3") (pintype "input"))
    )
    (net (code "99") (name "PORT_A3") (class "Default")
      (node (ref "IC1") (pin "13") (pinfunction "PA3_13") (pintype "bidirectional"))
      (node (ref "IC7") (pin "4") (pinfunction "4B_4") (pintype "input"))
    )
    (net (code "100") (name "PORT_A4") (class "Default")
      (node (ref "IC1") (pin "14") (pinfunction "PA4_14") (pintype "bidirectional"))
      (node (ref "IC7") (pin "5") (pinfunction "5B_5") (pintype "input"))
    )
    (net (code "101") (name "PORT_A5") (class "Default")
      (node (ref "IC1") (pin "15") (pinfunction "PA5_15") (pintype "bidirectional"))
      (node (ref "IC7") (pin "6") (pinfunction "6B_6") (pintype "input"))
    )
    (net (code "102") (name "PORT_A6") (class "Default")
      (node (ref "IC1") (pin "16") (pinfunction "PA6_16") (pintype "bidirectional"))
      (node (ref "IC7") (pin "7") (pinfunction "7B_7") (pintype "input"))
    )
    (net (code "103") (name "PORT_B0") (class "Default")
      (node (ref "IC1") (pin "18") (pinfunction "PB0_18") (pintype "bidirectional"))
      (node (ref "IC8") (pin "1") (pinfunction "1B_1") (pintype "input"))
    )
    (net (code "104") (name "PORT_B1") (class "Default")
      (node (ref "IC1") (pin "19") (pinfunction "PB1_19") (pintype "bidirectional"))
      (node (ref "IC8") (pin "2") (pinfunction "2B_2") (pintype "input"))
    )
    (net (code "105") (name "PORT_B2") (class "Default")
      (node (ref "IC1") (pin "20") (pinfunction "PB2_20") (pintype "bidirectional"))
      (node (ref "IC8") (pin "3") (pinfunction "3B_3") (pintype "input"))
    )
    (net (code "106") (name "PORT_B3") (class "Default")
      (node (ref "IC1") (pin "39") (pinfunction "PB3_39") (pintype "bidirectional"))
      (node (ref "IC8") (pin "4") (pinfunction "4B_4") (pintype "input"))
    )
    (net (code "107") (name "PORT_B4") (class "Default")
      (node (ref "IC1") (pin "40") (pinfunction "PB4_40") (pintype "bidirectional"))
      (node (ref "IC8") (pin "5") (pinfunction "5B_5") (pintype "input"))
    )
    (net (code "108") (name "PORT_B5") (class "Default")
      (node (ref "IC1") (pin "41") (pinfunction "PB5_41") (pintype "bidirectional"))
      (node (ref "IC8") (pin "6") (pinfunction "6B_6") (pintype "input"))
    )
    (net (code "109") (name "PORT_B6") (class "Default")
      (node (ref "IC1") (pin "42") (pinfunction "PB6_42") (pintype "bidirectional"))
      (node (ref "IC8") (pin "7") (pinfunction "7B_7") (pintype "input"))
    )
    (net (code "110") (name "SWCLK") (class "Default")
      (node (ref "IC1") (pin "37") (pinfunction "PA14_37") (pintype "bidirectional"))
      (node (ref "X1") (pin "2") (pinfunction "1_2") (pintype "passive"))
    )
    (net (code "111") (name "SWDIO") (class "Default")
      (node (ref "IC1") (pin "34") (pinfunction "PA13_34") (pintype "bidirectional"))
      (node (ref "X1") (pin "4") (pinfunction "1_4") (pintype "passive"))
    )
    (net (code "112") (name "UART_RX") (class "Default")
      (node (ref "IC1") (pin "31") (pinfunction "PA10_31") (pintype "bidirectional"))
      (node (ref "X2") (pin "28") (pinfunction "1_28") (pintype "passive"))
    )
    (net (code "113") (name "UART_TX") (class "Default")
      (node (ref "IC1") (pin "30") (pinfunction "PA9_30") (pintype "bidirectional"))
      (node (ref "IC2") (pin "2") (pinfunction "I_2") (pintype "input"))
      (node (ref "RN2") (pin "1") (pinfunction "1_1") (pintype "passive"))
    )
    (net (code "114") (name "unconnected-(IC1-PA8-Pad29)") (class "Default")
      (node (ref "IC1") (pin "29") (pinfunction "PA8_29") (pintype "bidirectional"))
    )
    (net (code "115") (name "unconnected-(IC1-PA11-Pad32)") (class "Default")
      (node (ref "IC1") (pin "32") (pinfunction "PA11_32") (pintype "bidirectional"))
    )
    (net (code "116") (name "unconnected-(IC1-PB8-Pad45)") (class "Default")
      (node (ref "IC1") (pin "45") (pinfunction "PB8_45") (pintype "bidirectional"))
    )
    (net (code "117") (name "unconnected-(IC1-PB9-Pad46)") (class "Default")
      (node (ref "IC1") (pin "46") (pinfunction "PB9_46") (pintype "bidirectional"))
    )
    (net (code "118") (name "unconnected-(IC1-PB11-Pad22)") (class "Default")
      (node (ref "IC1") (pin "22") (pinfunction "PB11_22") (pintype "bidirectional"))
    )
    (net (code "119") (name "unconnected-(IC1-PC13-Pad2)") (class "Default")
      (node (ref "IC1") (pin "2") (pinfunction "PC13_2") (pintype "bidirectional"))
    )
    (net (code "120") (name "unconnected-(IC1-PC14-OSC32_IN-Pad3)") (class "Default")
      (node (ref "IC1") (pin "3") (pinfunction "PC14-OSC32_IN_3") (pintype "bidirectional"))
    )
    (net (code "121") (name "unconnected-(IC1-PF0-OSC_IN-Pad5)") (class "Default")
      (node (ref "IC1") (pin "5") (pinfunction "PF0-OSC_IN_5") (pintype "bidirectional"))
    )
    (net (code "122") (name "unconnected-(IC1-PF6-Pad35)") (class "Default")
      (node (ref "IC1") (pin "35") (pinfunction "PF6_35") (pintype "bidirectional"))
    )
    (net (code "123") (name "unconnected-(IC1-PF7-Pad36)") (class "Default")
      (node (ref "IC1") (pin "36") (pinfunction "PF7_36") (pintype "bidirectional"))
    )
    (net (code "124") (name "unconnected-(IC6-ADJ-Pad1)") (class "Default")
      (node (ref "IC6") (pin "1") (pinfunction "ADJ_1") (pintype "passive"))
    )
    (net (code "125") (name "unconnected-(X2-Pad1)") (class "Default")
      (node (ref "X2") (pin "1") (pinfunction "1_1") (pintype "passive"))
    )
    (net (code "126") (name "unconnected-(X2L-1-Pad2)") (class "Default")
      (node (ref "X2") (pin "2") (pinfunction "1_2") (pintype "passive"))
    )
    (net (code "127") (name "unconnected-(X2N-1-Pad21)") (class "Default")
      (node (ref "X2") (pin "21") (pinfunction "1_21") (pintype "passive"))
    )
    (net (code "128") (name "unconnected-(X2O-1-Pad22)") (class "Default")
      (node (ref "X2") (pin "22") (pinfunction "1_22") (pintype "passive"))
    )
    (net (code "129") (name "unconnected-(X2V-1-Pad3)") (class "Default")
      (node (ref "X2") (pin "3") (pinfunction "1_3") (pintype "passive"))
    )
    (net (code "130") (name "unconnected-(X3-Pad1)") (class "Default")
      (node (ref "X3") (pin "1") (pinfunction "1_1") (pintype "passive"))
    )
    (net (code "131") (name "unconnected-(X3C-1-Pad2)") (class "Default")
      (node (ref "X3") (pin "2") (pinfunction "1_2") (pintype "passive"))
    )
    (net (code "132") (name "unconnected-(X3F-1-Pad5)") (class "Default")
      (node (ref "X3") (pin "5") (pinfunction "1_5") (pintype "passive"))
    )
    (net (code "133") (name "unconnected-(X3G-1-Pad6)") (class "Default")
      (node (ref "X3") (pin "6") (pinfunction "1_6") (pintype "passive"))
    )
    (net (code "134") (name "unconnected-(X3H-1-Pad7)") (class "Default")
      (node (ref "X3") (pin "7") (pinfunction "1_7") (pintype "passive"))
    )
    (net (code "135") (name "unconnected-(X3I-1-Pad8)") (class "Default")
      (node (ref "X3") (pin "8") (pinfunction "1_8") (pintype "passive"))
    )
    (net (code "136") (name "unconnected-(X4-Pad1)") (class "Default")
      (node (ref "X4") (pin "1") (pinfunction "1_1") (pintype "passive"))
    )
    (net (code "137") (name "unconnected-(X4C-1-Pad2)") (class "Default")
      (node (ref "X4") (pin "2") (pinfunction "1_2") (pintype "passive"))
    )
    (net (code "138") (name "unconnected-(X4F-1-Pad5)") (class "Default")
      (node (ref "X4") (pin "5") (pinfunction "1_5") (pintype "passive"))
    )
    (net (code "139") (name "unconnected-(X4G-1-Pad6)") (class "Default")
      (node (ref "X4") (pin "6") (pinfunction "1_6") (pintype "passive"))
    )
    (net (code "140") (name "unconnected-(X4H-1-Pad7)") (class "Default")
      (node (ref "X4") (pin "7") (pinfunction "1_7") (pintype "passive"))
    )
    (net (code "141") (name "unconnected-(X4I-1-Pad8)") (class "Default")
      (node (ref "X4") (pin "8") (pinfunction "1_8") (pintype "passive"))
    )
  )
)
